# Sheet1.net
KiCad netlist of a schematic drawn in Altium Designer
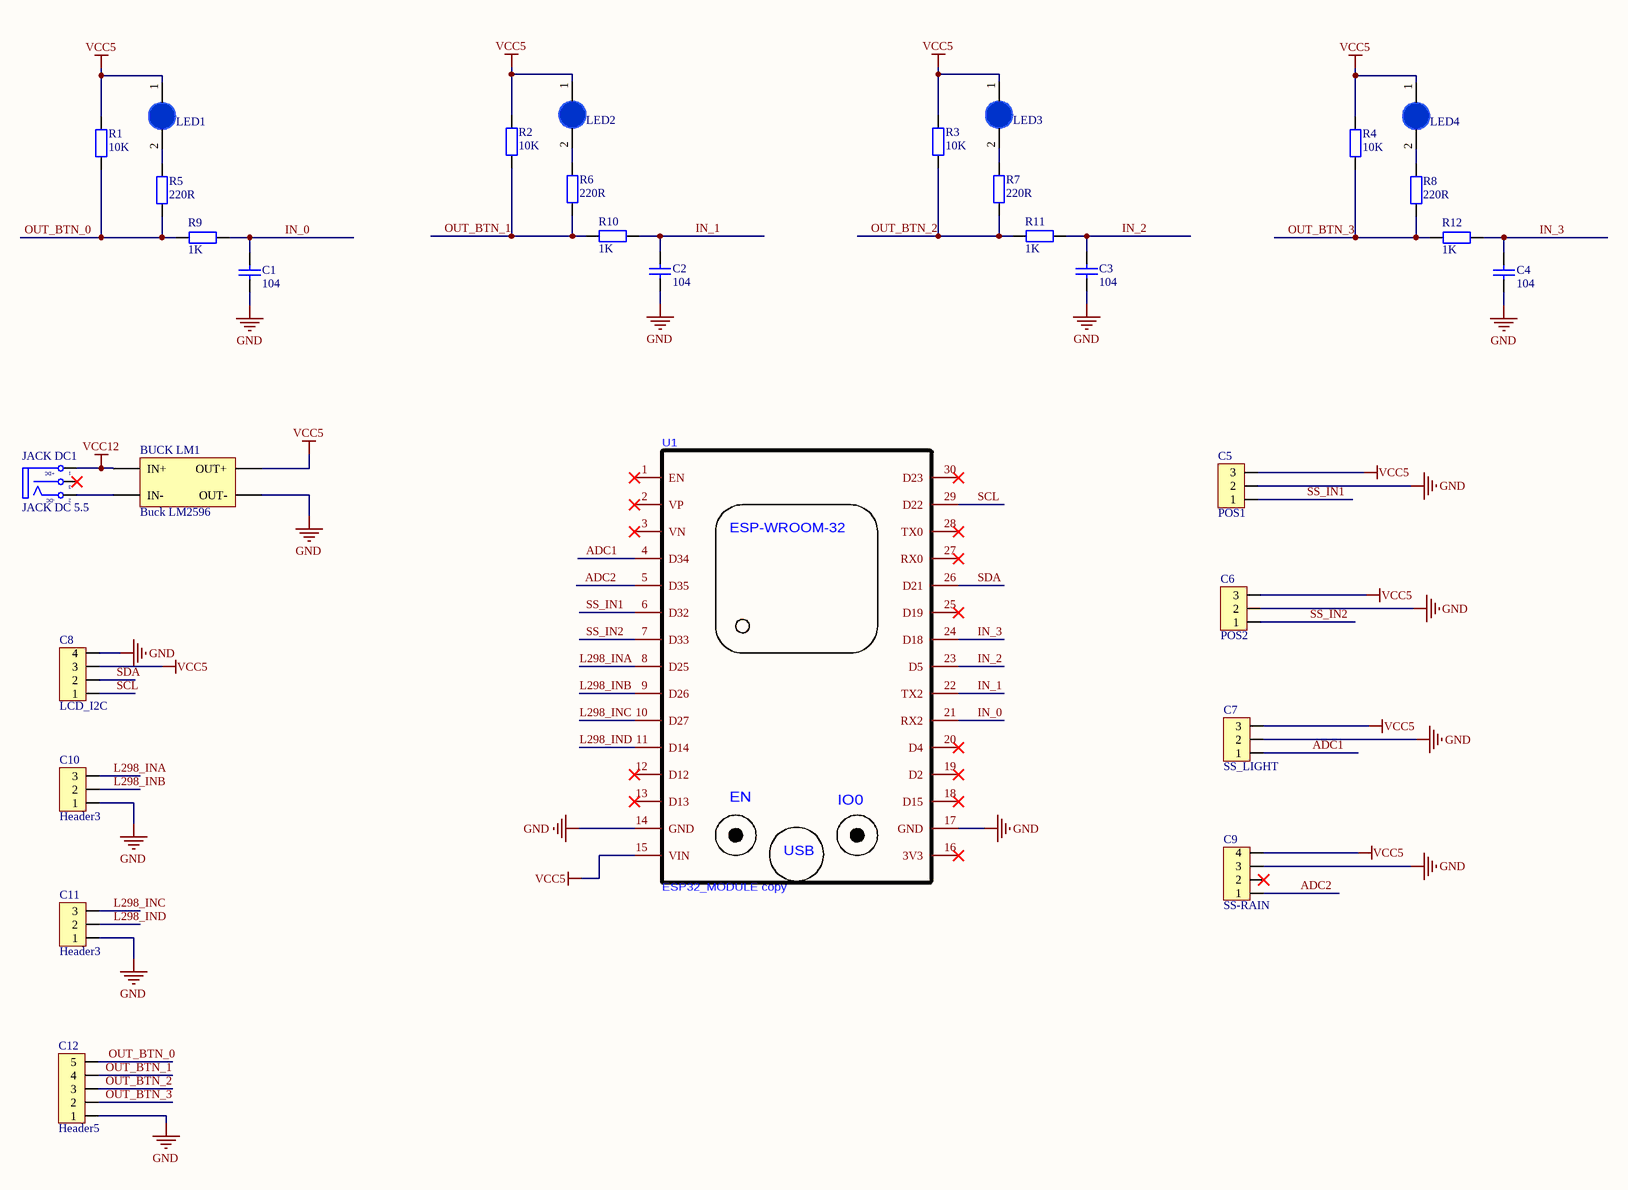
[diagram p0: Sheet1.SchDoc]

(export (version "E")
  (design (tool "Eeschema 10.0.6"))
  (components
    (comp (ref "BUCK LM1")
      (value "Buck LM2596")
      (footprint "BUCK LM2596")
      (libsource (lib "myLib_v1") (part "Buck LM2596"))
    )
    (comp (ref "C1")
      (value "104")
      (footprint "tu gom")
      (description "Cắm")
      (libsource (lib "Altium_Lib_by_KhueNguyenCreator") (part "Tu gom 104 50V"))
    )
    (comp (ref "C2")
      (value "104")
      (footprint "tu gom")
      (description "Cắm")
      (libsource (lib "Altium_Lib_by_KhueNguyenCreator") (part "Tu gom 104 50V"))
    )
    (comp (ref "C3")
      (value "104")
      (footprint "tu gom")
      (description "Cắm")
      (libsource (lib "Altium_Lib_by_KhueNguyenCreator") (part "Tu gom 104 50V"))
    )
    (comp (ref "C4")
      (value "104")
      (footprint "tu gom")
      (description "Cắm")
      (libsource (lib "Altium_Lib_by_KhueNguyenCreator") (part "Tu gom 104 50V"))
    )
    (comp (ref "C5")
      (value "POS1")
      (footprint "Header3")
      (description "Header IDC, 3 x 1 Pin Vertical 2.54mm Pitch (Non-Boxed, Male)")
      (fields
        (field (name "MANUFACTURER") "Würth Elektronik eiSos GmbH")
        (field (name "PARTNO") "613002143121")
        (field (name "CREATED BY") "Karrer Zheng")
      )
      (libsource (lib "myLib_v1") (part "Header3"))
    )
    (comp (ref "C6")
      (value "POS2")
      (footprint "Header3")
      (description "Header IDC, 3 x 1 Pin Vertical 2.54mm Pitch (Non-Boxed, Male)")
      (fields
        (field (name "MANUFACTURER") "Würth Elektronik eiSos GmbH")
        (field (name "PARTNO") "613002143121")
        (field (name "CREATED BY") "Karrer Zheng")
      )
      (libsource (lib "myLib_v1") (part "Header3"))
    )
    (comp (ref "C7")
      (value "SS_LIGHT")
      (footprint "Header3")
      (description "Header IDC, 3 x 1 Pin Vertical 2.54mm Pitch (Non-Boxed, Male)")
      (fields
        (field (name "MANUFACTURER") "Würth Elektronik eiSos GmbH")
        (field (name "PARTNO") "613002143121")
        (field (name "CREATED BY") "Karrer Zheng")
      )
      (libsource (lib "myLib_v1") (part "Header3"))
    )
    (comp (ref "C8")
      (value "LCD_I2C")
      (footprint "Header4")
      (description "Header IDC, 4 x 1 Pin Vertical 2.54mm Pitch (Non-Boxed, Male)")
      (fields
        (field (name "MANUFACTURER") "Würth Elektronik eiSos GmbH")
        (field (name "PARTNO") "613002143121")
        (field (name "CREATED BY") "Karrer Zheng")
      )
      (libsource (lib "myLib_v1") (part "Header4"))
    )
    (comp (ref "C9")
      (value "SS-RAIN")
      (footprint "Header4")
      (description "Header IDC, 4 x 1 Pin Vertical 2.54mm Pitch (Non-Boxed, Male)")
      (fields
        (field (name "MANUFACTURER") "Würth Elektronik eiSos GmbH")
        (field (name "PARTNO") "613002143121")
        (field (name "CREATED BY") "Karrer Zheng")
      )
      (libsource (lib "myLib_v1") (part "Header4"))
    )
    (comp (ref "C10")
      (value "Header3")
      (footprint "Header3")
      (description "Header IDC, 3 x 1 Pin Vertical 2.54mm Pitch (Non-Boxed, Male)")
      (fields
        (field (name "MANUFACTURER") "Würth Elektronik eiSos GmbH")
        (field (name "PARTNO") "613002143121")
        (field (name "CREATED BY") "Karrer Zheng")
      )
      (libsource (lib "myLib_v1") (part "Header3"))
    )
    (comp (ref "C11")
      (value "Header3")
      (footprint "Header3")
      (description "Header IDC, 3 x 1 Pin Vertical 2.54mm Pitch (Non-Boxed, Male)")
      (fields
        (field (name "MANUFACTURER") "Würth Elektronik eiSos GmbH")
        (field (name "PARTNO") "613002143121")
        (field (name "CREATED BY") "Karrer Zheng")
      )
      (libsource (lib "myLib_v1") (part "Header3"))
    )
    (comp (ref "C12")
      (value "Header5")
      (footprint "Header5")
      (description "Header IDC, 5 x 1 Pin Vertical 2.54mm Pitch (Non-Boxed, Male)")
      (fields
        (field (name "MANUFACTURER") "Würth Elektronik eiSos GmbH")
        (field (name "PARTNO") "613002143121")
        (field (name "CREATED BY") "Karrer Zheng")
      )
      (libsource (lib "myLib_v1") (part "Header5"))
    )
    (comp (ref "JACK DC1")
      (value "JACK DC 5.5")
      (footprint "JACK DC 5.5")
      (libsource (lib "Altium_Lib_by_KhueNguyenCreator") (part "JACK DC 5.5"))
    )
    (comp (ref "LED1")
      (value "LED 3mm")
      (footprint "LED-3MM-BLUE")
      (description "Cắm")
      (libsource (lib "myLib_v1") (part "LED 3mm Xanh Duong"))
    )
    (comp (ref "LED2")
      (value "LED 3mm")
      (footprint "LED-3MM-BLUE")
      (description "Cắm")
      (libsource (lib "myLib_v1") (part "LED 3mm Xanh Duong"))
    )
    (comp (ref "LED3")
      (value "LED 3mm")
      (footprint "LED-3MM-BLUE")
      (description "Cắm")
      (libsource (lib "myLib_v1") (part "LED 3mm Xanh Duong"))
    )
    (comp (ref "LED4")
      (value "LED 3mm")
      (footprint "LED-3MM-BLUE")
      (description "Cắm")
      (libsource (lib "myLib_v1") (part "LED 3mm Xanh Duong"))
    )
    (comp (ref "R1")
      (value "10K")
      (footprint "R1/4W")
      (description "Resistor 1/4W")
      (libsource (lib "myLib_v1") (part "R1/4W"))
    )
    (comp (ref "R2")
      (value "10K")
      (footprint "R1/4W")
      (description "Resistor 1/4W")
      (libsource (lib "myLib_v1") (part "R1/4W"))
    )
    (comp (ref "R3")
      (value "10K")
      (footprint "R1/4W")
      (description "Resistor 1/4W")
      (libsource (lib "myLib_v1") (part "R1/4W"))
    )
    (comp (ref "R4")
      (value "10K")
      (footprint "R1/4W")
      (description "Resistor 1/4W")
      (libsource (lib "myLib_v1") (part "R1/4W"))
    )
    (comp (ref "R5")
      (value "220R")
      (footprint "R1/4W")
      (description "Resistor 1/4W")
      (libsource (lib "myLib_v1") (part "R1/4W"))
    )
    (comp (ref "R6")
      (value "220R")
      (footprint "R1/4W")
      (description "Resistor 1/4W")
      (libsource (lib "myLib_v1") (part "R1/4W"))
    )
    (comp (ref "R7")
      (value "220R")
      (footprint "R1/4W")
      (description "Resistor 1/4W")
      (libsource (lib "myLib_v1") (part "R1/4W"))
    )
    (comp (ref "R8")
      (value "220R")
      (footprint "R1/4W")
      (description "Resistor 1/4W")
      (libsource (lib "myLib_v1") (part "R1/4W"))
    )
    (comp (ref "R9")
      (value "1K")
      (footprint "R1/4W")
      (description "Resistor 1/4W")
      (libsource (lib "myLib_v1") (part "R1/4W"))
    )
    (comp (ref "R10")
      (value "1K")
      (footprint "R1/4W")
      (description "Resistor 1/4W")
      (libsource (lib "myLib_v1") (part "R1/4W"))
    )
    (comp (ref "R11")
      (value "1K")
      (footprint "R1/4W")
      (description "Resistor 1/4W")
      (libsource (lib "myLib_v1") (part "R1/4W"))
    )
    (comp (ref "R12")
      (value "1K")
      (footprint "R1/4W")
      (description "Resistor 1/4W")
      (libsource (lib "myLib_v1") (part "R1/4W"))
    )
    (comp (ref "U1")
      (value "ESP32_MODULE copy")
      (footprint "ESP32-WIFIMODULE-FOOTPRINT")
      (libsource (lib "myLib_v1") (part "ESP32_MODULE copy"))
    )
  )
  (nets
    (net (code "1") (name "/ADC1") (class "Default")
      (node (ref "C7") (pin "1") (pinfunction "1_1") (pintype "passive"))
      (node (ref "U1") (pin "4") (pinfunction "D34_4") (pintype "passive"))
    )
    (net (code "2") (name "/ADC2") (class "Default")
      (node (ref "C9") (pin "1") (pinfunction "1_1") (pintype "passive"))
      (node (ref "U1") (pin "5") (pinfunction "D35_5") (pintype "passive"))
    )
    (net (code "3") (name "/IN_0") (class "Default")
      (node (ref "C1") (pin "1") (pinfunction "1_1") (pintype "passive"))
      (node (ref "R9") (pin "1") (pinfunction "1_1") (pintype "passive"))
      (node (ref "U1") (pin "21") (pinfunction "RX2_21") (pintype "passive"))
    )
    (net (code "4") (name "/IN_1") (class "Default")
      (node (ref "C2") (pin "1") (pinfunction "1_1") (pintype "passive"))
      (node (ref "R10") (pin "1") (pinfunction "1_1") (pintype "passive"))
      (node (ref "U1") (pin "22") (pinfunction "TX2_22") (pintype "passive"))
    )
    (net (code "5") (name "/IN_2") (class "Default")
      (node (ref "C3") (pin "1") (pinfunction "1_1") (pintype "passive"))
      (node (ref "R11") (pin "1") (pinfunction "1_1") (pintype "passive"))
      (node (ref "U1") (pin "23") (pinfunction "D5_23") (pintype "passive"))
    )
    (net (code "6") (name "/IN_3") (class "Default")
      (node (ref "C4") (pin "1") (pinfunction "1_1") (pintype "passive"))
      (node (ref "R12") (pin "1") (pinfunction "1_1") (pintype "passive"))
      (node (ref "U1") (pin "24") (pinfunction "D18_24") (pintype "passive"))
    )
    (net (code "7") (name "/L298_INA") (class "Default")
      (node (ref "C10") (pin "3") (pinfunction "3_3") (pintype "passive"))
      (node (ref "U1") (pin "8") (pinfunction "D25_8") (pintype "passive"))
    )
    (net (code "8") (name "/L298_INB") (class "Default")
      (node (ref "C10") (pin "2") (pinfunction "2_2") (pintype "passive"))
      (node (ref "U1") (pin "9") (pinfunction "D26_9") (pintype "passive"))
    )
    (net (code "9") (name "/L298_INC") (class "Default")
      (node (ref "C11") (pin "3") (pinfunction "3_3") (pintype "passive"))
      (node (ref "U1") (pin "10") (pinfunction "D27_10") (pintype "passive"))
    )
    (net (code "10") (name "/L298_IND") (class "Default")
      (node (ref "C11") (pin "2") (pinfunction "2_2") (pintype "passive"))
      (node (ref "U1") (pin "11") (pinfunction "D14_11") (pintype "passive"))
    )
    (net (code "11") (name "/OUT_BTN_0") (class "Default")
      (node (ref "C12") (pin "5") (pinfunction "5_5") (pintype "passive"))
      (node (ref "R1") (pin "1") (pinfunction "1_1") (pintype "passive"))
      (node (ref "R5") (pin "1") (pinfunction "1_1") (pintype "passive"))
      (node (ref "R9") (pin "2") (pinfunction "2_2") (pintype "passive"))
    )
    (net (code "12") (name "/OUT_BTN_1") (class "Default")
      (node (ref "C12") (pin "4") (pinfunction "4_4") (pintype "passive"))
      (node (ref "R10") (pin "2") (pinfunction "2_2") (pintype "passive"))
      (node (ref "R2") (pin "1") (pinfunction "1_1") (pintype "passive"))
      (node (ref "R6") (pin "1") (pinfunction "1_1") (pintype "passive"))
    )
    (net (code "13") (name "/OUT_BTN_2") (class "Default")
      (node (ref "C12") (pin "3") (pinfunction "3_3") (pintype "passive"))
      (node (ref "R11") (pin "2") (pinfunction "2_2") (pintype "passive"))
      (node (ref "R3") (pin "1") (pinfunction "1_1") (pintype "passive"))
      (node (ref "R7") (pin "1") (pinfunction "1_1") (pintype "passive"))
    )
    (net (code "14") (name "/OUT_BTN_3") (class "Default")
      (node (ref "C12") (pin "2") (pinfunction "2_2") (pintype "passive"))
      (node (ref "R12") (pin "2") (pinfunction "2_2") (pintype "passive"))
      (node (ref "R4") (pin "1") (pinfunction "1_1") (pintype "passive"))
      (node (ref "R8") (pin "1") (pinfunction "1_1") (pintype "passive"))
    )
    (net (code "15") (name "/SCL") (class "Default")
      (node (ref "C8") (pin "1") (pinfunction "1_1") (pintype "passive"))
      (node (ref "U1") (pin "29") (pinfunction "D22_29") (pintype "passive"))
    )
    (net (code "16") (name "/SDA") (class "Default")
      (node (ref "C8") (pin "2") (pinfunction "2_2") (pintype "passive"))
      (node (ref "U1") (pin "26") (pinfunction "D21_26") (pintype "passive"))
    )
    (net (code "17") (name "/SS_IN1") (class "Default")
      (node (ref "C5") (pin "1") (pinfunction "1_1") (pintype "passive"))
      (node (ref "U1") (pin "6") (pinfunction "D32_6") (pintype "passive"))
    )
    (net (code "18") (name "/SS_IN2") (class "Default")
      (node (ref "C6") (pin "1") (pinfunction "1_1") (pintype "passive"))
      (node (ref "U1") (pin "7") (pinfunction "D33_7") (pintype "passive"))
    )
    (net (code "19") (name "GND") (class "Default")
      (node (ref "BUCK LM1") (pin "3") (pinfunction "OUT-_3") (pintype "passive"))
      (node (ref "C1") (pin "2") (pinfunction "2_2") (pintype "passive"))
      (node (ref "C10") (pin "1") (pinfunction "1_1") (pintype "passive"))
      (node (ref "C11") (pin "1") (pinfunction "1_1") (pintype "passive"))
      (node (ref "C12") (pin "1") (pinfunction "1_1") (pintype "passive"))
      (node (ref "C2") (pin "2") (pinfunction "2_2") (pintype "passive"))
      (node (ref "C3") (pin "2") (pinfunction "2_2") (pintype "passive"))
      (node (ref "C4") (pin "2") (pinfunction "2_2") (pintype "passive"))
      (node (ref "C5") (pin "2") (pinfunction "2_2") (pintype "passive"))
      (node (ref "C6") (pin "2") (pinfunction "2_2") (pintype "passive"))
      (node (ref "C7") (pin "2") (pinfunction "2_2") (pintype "passive"))
      (node (ref "C8") (pin "4") (pinfunction "4_4") (pintype "passive"))
      (node (ref "C9") (pin "3") (pinfunction "3_3") (pintype "passive"))
      (node (ref "U1") (pin "14") (pinfunction "GND_14") (pintype "passive"))
      (node (ref "U1") (pin "17") (pinfunction "GND_17") (pintype "passive"))
    )
    (net (code "20") (name "Net-(BUCK LM1-IN-)") (class "Default")
      (node (ref "BUCK LM1") (pin "2") (pinfunction "IN-_2") (pintype "passive"))
      (node (ref "JACK DC1") (pin "2") (pinfunction "TN_2") (pintype "passive"))
    )
    (net (code "21") (name "Net-(LED1-K)") (class "Default")
      (node (ref "LED1") (pin "2") (pinfunction "K_2") (pintype "passive"))
      (node (ref "R5") (pin "2") (pinfunction "2_2") (pintype "passive"))
    )
    (net (code "22") (name "Net-(LED2-K)") (class "Default")
      (node (ref "LED2") (pin "2") (pinfunction "K_2") (pintype "passive"))
      (node (ref "R6") (pin "2") (pinfunction "2_2") (pintype "passive"))
    )
    (net (code "23") (name "Net-(LED3-K)") (class "Default")
      (node (ref "LED3") (pin "2") (pinfunction "K_2") (pintype "passive"))
      (node (ref "R7") (pin "2") (pinfunction "2_2") (pintype "passive"))
    )
    (net (code "24") (name "Net-(LED4-K)") (class "Default")
      (node (ref "LED4") (pin "2") (pinfunction "K_2") (pintype "passive"))
      (node (ref "R8") (pin "2") (pinfunction "2_2") (pintype "passive"))
    )
    (net (code "25") (name "VCC5") (class "Default")
      (node (ref "BUCK LM1") (pin "4") (pinfunction "OUT+_4") (pintype "passive"))
      (node (ref "C5") (pin "3") (pinfunction "3_3") (pintype "passive"))
      (node (ref "C6") (pin "3") (pinfunction "3_3") (pintype "passive"))
      (node (ref "C7") (pin "3") (pinfunction "3_3") (pintype "passive"))
      (node (ref "C8") (pin "3") (pinfunction "3_3") (pintype "passive"))
      (node (ref "C9") (pin "4") (pinfunction "4_4") (pintype "passive"))
      (node (ref "LED1") (pin "1") (pinfunction "A_1") (pintype "passive"))
      (node (ref "LED2") (pin "1") (pinfunction "A_1") (pintype "passive"))
      (node (ref "LED3") (pin "1") (pinfunction "A_1") (pintype "passive"))
      (node (ref "LED4") (pin "1") (pinfunction "A_1") (pintype "passive"))
      (node (ref "R1") (pin "2") (pinfunction "2_2") (pintype "passive"))
      (node (ref "R2") (pin "2") (pinfunction "2_2") (pintype "passive"))
      (node (ref "R3") (pin "2") (pinfunction "2_2") (pintype "passive"))
      (node (ref "R4") (pin "2") (pinfunction "2_2") (pintype "passive"))
      (node (ref "U1") (pin "15") (pinfunction "VIN_15") (pintype "passive"))
    )
    (net (code "26") (name "VCC12") (class "Default")
      (node (ref "BUCK LM1") (pin "1") (pinfunction "IN+_1") (pintype "passive"))
      (node (ref "JACK DC1") (pin "1") (pinfunction "T_1") (pintype "passive"))
    )
    (net (code "27") (name "unconnected-(C9-Pad2)") (class "Default")
      (node (ref "C9") (pin "2") (pinfunction "2_2") (pintype "passive+no_connect"))
    )
    (net (code "28") (name "unconnected-(JACK DC1-S-Pad3)") (class "Default")
      (node (ref "JACK DC1") (pin "3") (pinfunction "S_3") (pintype "power_in+no_connect"))
    )
    (net (code "29") (name "unconnected-(U1-3V3-Pad16)") (class "Default")
      (node (ref "U1") (pin "16") (pinfunction "3V3_16") (pintype "passive+no_connect"))
    )
    (net (code "30") (name "unconnected-(U1-D2-Pad19)") (class "Default")
      (node (ref "U1") (pin "19") (pinfunction "D2_19") (pintype "passive+no_connect"))
    )
    (net (code "31") (name "unconnected-(U1-D4-Pad20)") (class "Default")
      (node (ref "U1") (pin "20") (pinfunction "D4_20") (pintype "passive+no_connect"))
    )
    (net (code "32") (name "unconnected-(U1-D12-Pad12)") (class "Default")
      (node (ref "U1") (pin "12") (pinfunction "D12_12") (pintype "passive+no_connect"))
    )
    (net (code "33") (name "unconnected-(U1-D13-Pad13)") (class "Default")
      (node (ref "U1") (pin "13") (pinfunction "D13_13") (pintype "passive+no_connect"))
    )
    (net (code "34") (name "unconnected-(U1-D15-Pad18)") (class "Default")
      (node (ref "U1") (pin "18") (pinfunction "D15_18") (pintype "passive+no_connect"))
    )
    (net (code "35") (name "unconnected-(U1-D19-Pad25)") (class "Default")
      (node (ref "U1") (pin "25") (pinfunction "D19_25") (pintype "passive+no_connect"))
    )
    (net (code "36") (name "unconnected-(U1-D23-Pad30)") (class "Default")
      (node (ref "U1") (pin "30") (pinfunction "D23_30") (pintype "passive+no_connect"))
    )
    (net (code "37") (name "unconnected-(U1-EN-Pad1)") (class "Default")
      (node (ref "U1") (pin "1") (pinfunction "EN_1") (pintype "passive+no_connect"))
    )
    (net (code "38") (name "unconnected-(U1-RX0-Pad27)") (class "Default")
      (node (ref "U1") (pin "27") (pinfunction "RX0_27") (pintype "passive+no_connect"))
    )
    (net (code "39") (name "unconnected-(U1-TX0-Pad28)") (class "Default")
      (node (ref "U1") (pin "28") (pinfunction "TX0_28") (pintype "passive+no_connect"))
    )
    (net (code "40") (name "unconnected-(U1-VN-Pad3)") (class "Default")
      (node (ref "U1") (pin "3") (pinfunction "VN_3") (pintype "passive+no_connect"))
    )
    (net (code "41") (name "unconnected-(U1-VP-Pad2)") (class "Default")
      (node (ref "U1") (pin "2") (pinfunction "VP_2") (pintype "passive+no_connect"))
    )
  )
)
